# TPS61169_SEPIC_60_mA_LED_Driver_V2_0.net
KiCad netlist of a schematic drawn in Altium Designer
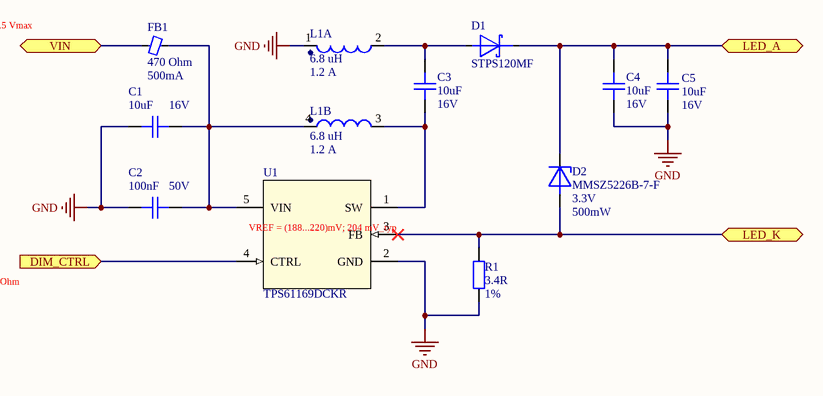
[diagram p0: TPS61169_SEPIC_60_mA_LED_Driver_V2.0.SchDoc]

(export (version "E")
  (design (tool "Eeschema 10.0.6"))
  (components
    (comp (ref "C1")
      (value "CAP CER 10UF 16V X5R 0603")
      (footprint "C0603")
      (description "10µF ±10% 16V Ceramic Capacitor X5R 0603 (1608 Metric)")
      (fields
        (field (name "MANUFACTURER") "Murata")
        (field (name "MANUFACTURER PART NUMBER") "GRM188R61C106KAALJ")
        (field (name "VOLTAGE RATING") "16V")
        (field (name "CAPACITANCE") "10uF")
      )
      (libsource (lib "capacitors_smd") (part "CAP CER 10UF 16V X5R 0603"))
    )
    (comp (ref "C2")
      (value "CAP CER 0.1UF 50V X7R 0402")
      (footprint "C0402")
      (description "0.1µF ±10% 50V Ceramic Capacitor X7R 0402 (1005 Metric)")
      (fields
        (field (name "MANUFACTURER") "TDK")
        (field (name "MANUFACTURER PART NUMBER") "CGA2B3X7R1H104K050BB")
        (field (name "CAPACITANCE") "100nF")
        (field (name "VOLTAGE") "50V")
      )
      (libsource (lib "capacitors_smd") (part "CAP CER 0.1UF 50V X7R 0402"))
    )
    (comp (ref "C3")
      (value "CAP CER 10UF 16V X7R 0805")
      (footprint "C0805")
      (description "10µF ±10% 16V Ceramic Capacitor X7R 0805 (2012 Metric)")
      (fields
        (field (name "MANUFACTURER") "Samsung")
        (field (name "MANUFACTURER PART NUMBER") "CL21B106KOQNNNG")
        (field (name "CAPACITANCE") "10uF")
        (field (name "VOLTAGE RATING") "16V")
      )
      (libsource (lib "capacitors_smd") (part "CAP CER 10UF 16V X7R 0805"))
    )
    (comp (ref "C4")
      (value "CAP CER 10UF 16V X5R 0603")
      (footprint "C0603")
      (description "10µF ±10% 16V Ceramic Capacitor X5R 0603 (1608 Metric)")
      (fields
        (field (name "MANUFACTURER") "Murata")
        (field (name "MANUFACTURER PART NUMBER") "GRM188R61C106KAALJ")
        (field (name "CAPACITANCE") "10uF")
        (field (name "VOLTAGE RATING") "16V")
      )
      (libsource (lib "capacitors_smd") (part "CAP CER 10UF 16V X5R 0603"))
    )
    (comp (ref "C5")
      (value "CAP CER 10UF 16V X5R 0603")
      (footprint "C0603")
      (description "10µF ±10% 16V Ceramic Capacitor X5R 0603 (1608 Metric)")
      (fields
        (field (name "MANUFACTURER") "Murata")
        (field (name "MANUFACTURER PART NUMBER") "GRM188R61C106KAALJ")
        (field (name "VOLTAGE RATING") "16V")
        (field (name "CAPACITANCE") "10uF")
      )
      (libsource (lib "capacitors_smd") (part "CAP CER 10UF 16V X5R 0603"))
    )
    (comp (ref "D1")
      (value "STPS120MF")
      (footprint "SODFL375X95-2N")
      (description "Diode Schottky 20V 1A Surface Mount STmite Flat")
      (fields (field (name "MANUFACTURER") "STMicroelectronics"))
      (libsource (lib "diodes_schottky") (part "DIODE SCHOTTKY 20V 1A STMITEFLAT"))
    )
    (comp (ref "D2")
      (value "MMSZ5226B-7-F")
      (footprint "SOD-123")
      (description "Zener Diode ±5% Surface Mount SOD-123")
      (fields
        (field (name "MANUFACTURER") "Diodes")
        (field (name "TOLERANCE") "5%")
        (field (name "WORKING VOLTAGE") "3.3V")
        (field (name "POWER RATING") "500mW")
      )
      (libsource (lib "diodes_zener") (part "DIODE ZENER 3.3V 500MW SOD123"))
    )
    (comp (ref "FB1")
      (value "FERRITE BEAD 470 OHM 0603 1LN")
      (footprint "L0603")
      (description "470 Ohms @ 100MHz 1  Ferrite Bead 0603 (1608 Metric) 500mA 210mOhm")
      (fields
        (field (name "MANUFACTURER") "Murata")
        (field (name "MANUFACTURER PART NUMBER") "BLM18EG471SN1D")
        (field (name "IMPEDANCE") "470 Ohm")
        (field (name "CURRENT RATING") "500mA")
      )
      (libsource (lib "ferrite_beads") (part "FERRITE BEAD 470 OHM 0603 1LN"))
    )
    (comp (ref "L1")
      (value "FIXED IND COUIPLED 6.8UH 1.2A 160 mOHM SMD")
      (footprint "IND_LPD5030")
      (description "6.8µH Shielded Coupled Inductors 1.2A 160mOhm Max 1919 (4.8x4.8 Metric)")
      (fields
        (field (name "MANUFACTURER") "Coilcraft")
        (field (name "MANUFACTURER PART NUMBER") "LPD5030-682MR")
        (field (name "INDUCTANCE") "6.8 uH")
        (field (name "MAXIMUM DC CURRENT") "1.2 A")
      )
      (libsource (lib "") (part "FIXED IND COUIPLED 6.8UH 1.2A 160 mOHM SMD_1"))
    )
    (comp (ref "R1")
      (value "RES SMD 3.4 OHM 1% 1/10W 0603")
      (footprint "R0603")
      (description "3.4 Ohms ±1% 0.1W, 1/10W Chip Resistor 0603 (1608 Metric) Automotive AEC-Q200 Thick Film")
      (fields
        (field (name "MANUFACTURER PART NUMBER") "CRCW06033R40FKEA")
        (field (name "MANUFACTURER") "Vishay Dale")
        (field (name "RESISTANCE") "3.4R")
        (field (name "TOLERANCE") "1%")
      )
      (libsource (lib "Control_Board_Model") (part "RES SMD 3.4 OHM 1% 1/10W 0603"))
    )
    (comp (ref "U1")
      (value "TPS61169DCKR")
      (footprint "DCK0005A_L")
      (description "LED Driver IC 1 Output DC DC Regulator Step-Up (Boost) PWM Dimming 1.8A (Switch) SC-70-5")
      (fields (field (name "MANUFACTURER") "Texas Instruments"))
      (libsource (lib "dcdc_converters") (part "IC TPS61169 WLED BACKLIGHT DRIVER SC70-5"))
    )
  )
  (nets
    (net (code "1") (name "/DIM_CTRL") (class "Default")
      (node (ref "U1") (pin "4") (pinfunction "CTRL_4") (pintype "input"))
    )
    (net (code "2") (name "/LED_A") (class "Default")
      (node (ref "C4") (pin "2") (pinfunction "2_2") (pintype "passive"))
      (node (ref "C5") (pin "1") (pinfunction "1_1") (pintype "passive"))
      (node (ref "D1") (pin "1") (pinfunction "K_1") (pintype "passive"))
      (node (ref "D2") (pin "1") (pinfunction "K_1") (pintype "passive"))
    )
    (net (code "3") (name "/LED_K") (class "Default")
      (node (ref "D2") (pin "2") (pinfunction "A_2") (pintype "passive"))
      (node (ref "R1") (pin "2") (pinfunction "2_2") (pintype "passive"))
      (node (ref "U1") (pin "3") (pinfunction "FB_3") (pintype "input"))
    )
    (net (code "4") (name "/VIN") (class "Default")
      (node (ref "FB1") (pin "1") (pinfunction "1_1") (pintype "passive"))
    )
    (net (code "5") (name "GND") (class "Default")
      (node (ref "C1") (pin "1") (pinfunction "1_1") (pintype "passive"))
      (node (ref "C2") (pin "2") (pinfunction "2_2") (pintype "passive"))
      (node (ref "C4") (pin "1") (pinfunction "1_1") (pintype "passive"))
      (node (ref "C5") (pin "2") (pinfunction "2_2") (pintype "passive"))
      (node (ref "L1") (pin "1") (pinfunction "1_1") (pintype "passive"))
      (node (ref "R1") (pin "1") (pinfunction "1_1") (pintype "passive"))
      (node (ref "U1") (pin "2") (pinfunction "GND_2") (pintype "power_in"))
    )
    (net (code "6") (name "Net-(D1-A)") (class "Default")
      (node (ref "C3") (pin "2") (pinfunction "2_2") (pintype "passive"))
      (node (ref "D1") (pin "2") (pinfunction "A_2") (pintype "passive"))
      (node (ref "L1") (pin "2") (pinfunction "2_2") (pintype "passive"))
    )
    (net (code "7") (name "Net-(U1-SW)") (class "Default")
      (node (ref "C3") (pin "1") (pinfunction "1_1") (pintype "passive"))
      (node (ref "L1") (pin "3") (pinfunction "3_3") (pintype "passive"))
      (node (ref "U1") (pin "1") (pinfunction "SW_1") (pintype "power_in"))
    )
    (net (code "8") (name "Net-(U1-VIN)") (class "Default")
      (node (ref "C1") (pin "2") (pinfunction "2_2") (pintype "passive"))
      (node (ref "C2") (pin "1") (pinfunction "1_1") (pintype "passive"))
      (node (ref "FB1") (pin "2") (pinfunction "2_2") (pintype "passive"))
      (node (ref "L1") (pin "4") (pinfunction "4_4") (pintype "passive"))
      (node (ref "U1") (pin "5") (pinfunction "VIN_5") (pintype "power_in"))
    )
  )
)
